# radio_FM.net
KiCad netlist of a schematic drawn in EAGLE
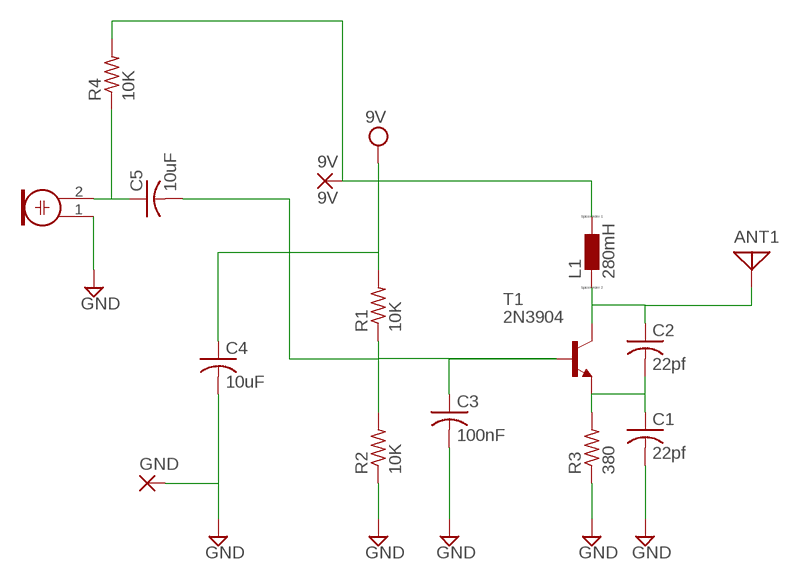
[diagram p0: schematic, sheet 1]

(export (version "E")
  (design (tool "Eeschema 10.0.6"))
  (components
    (comp (ref "9V")
      (value "9V")
      (footprint "eagle-import:1,6_0,8")
      (libsource (lib "eagle-import") (part "1,6/0,8"))
    )
    (comp (ref "ANT1")
      (value "ANTENNA")
      (footprint "eagle-import:PAD-01")
      (libsource (lib "eagle-import") (part "ANTENNA"))
    )
    (comp (ref "C1")
      (value "22pf")
      (footprint "eagle-import:C050-025X075")
      (libsource (lib "eagle-import") (part "C-US050-025X075"))
    )
    (comp (ref "C2")
      (value "22pf")
      (footprint "eagle-import:C050-025X075")
      (libsource (lib "eagle-import") (part "C-US050-025X075"))
    )
    (comp (ref "C3")
      (value "100nF")
      (footprint "eagle-import:C050-025X075")
      (libsource (lib "eagle-import") (part "C-US050-025X075"))
    )
    (comp (ref "C4")
      (value "10uF")
      (footprint "eagle-import:C050-025X075")
      (libsource (lib "eagle-import") (part "C-US050-025X075"))
    )
    (comp (ref "C5")
      (value "10uF")
      (footprint "eagle-import:C050-025X075")
      (libsource (lib "eagle-import") (part "C-US050-025X075"))
    )
    (comp (ref "GND")
      (value "1,6/0,8")
      (footprint "eagle-import:1,6_0,8")
      (libsource (lib "eagle-import") (part "1,6/0,8"))
    )
    (comp (ref "L1")
      (value "280mH")
      (footprint "eagle-import:0207_10")
      (libsource (lib "eagle-import") (part "L0207/10"))
    )
    (comp (ref "M1")
      (value "ELECTRET_MICROPHON-F6035AP")
      (footprint "eagle-import:F6035AP")
      (libsource (lib "eagle-import") (part "ELECTRET_MICROPHON-F6035AP"))
    )
    (comp (ref "R1")
      (value "10K")
      (footprint "eagle-import:0207_7")
      (libsource (lib "eagle-import") (part "R-US_0207/7"))
    )
    (comp (ref "R2")
      (value "10K")
      (footprint "eagle-import:0207_7")
      (libsource (lib "eagle-import") (part "R-US_0207/7"))
    )
    (comp (ref "R3")
      (value "380")
      (footprint "eagle-import:0207_7")
      (libsource (lib "eagle-import") (part "R-US_0207/7"))
    )
    (comp (ref "R4")
      (value "10K")
      (footprint "eagle-import:0207_7")
      (libsource (lib "eagle-import") (part "R-US_0207/7"))
    )
    (comp (ref "T1")
      (value "2N3904")
      (footprint "eagle-import:TO92")
      (libsource (lib "eagle-import") (part "2N3904"))
    )
  )
  (nets
    (net (code "1") (name "9V") (class "Default")
      (node (ref "9V") (pin "1") (pinfunction "P_1") (pintype "passive"))
      (node (ref "C4") (pin "1") (pinfunction "1_1") (pintype "passive"))
      (node (ref "L1") (pin "1") (pinfunction "1_1") (pintype "passive"))
      (node (ref "R1") (pin "2") (pinfunction "2_2") (pintype "passive"))
      (node (ref "R4") (pin "2") (pinfunction "2_2") (pintype "passive"))
    )
    (net (code "2") (name "GND") (class "Default")
      (node (ref "C1") (pin "2") (pinfunction "2_2") (pintype "passive"))
      (node (ref "C3") (pin "2") (pinfunction "2_2") (pintype "passive"))
      (node (ref "C4") (pin "2") (pinfunction "2_2") (pintype "passive"))
      (node (ref "GND") (pin "1") (pinfunction "P_1") (pintype "passive"))
      (node (ref "M1") (pin "1") (pinfunction "1_1") (pintype "passive"))
      (node (ref "R2") (pin "1") (pinfunction "1_1") (pintype "passive"))
      (node (ref "R3") (pin "1") (pinfunction "1_1") (pintype "passive"))
    )
    (net (code "3") (name "Net-(C5-Pad1)") (class "Default")
      (node (ref "C5") (pin "1") (pinfunction "1_1") (pintype "passive"))
      (node (ref "M1") (pin "2") (pinfunction "2_2") (pintype "passive"))
      (node (ref "R4") (pin "1") (pinfunction "1_1") (pintype "passive"))
    )
    (net (code "4") (name "Net-(T1-B)") (class "Default")
      (node (ref "C3") (pin "1") (pinfunction "1_1") (pintype "passive"))
      (node (ref "C5") (pin "2") (pinfunction "2_2") (pintype "passive"))
      (node (ref "R1") (pin "1") (pinfunction "1_1") (pintype "passive"))
      (node (ref "R2") (pin "2") (pinfunction "2_2") (pintype "passive"))
      (node (ref "T1") (pin "2") (pinfunction "B_2") (pintype "passive"))
    )
    (net (code "5") (name "Net-(T1-C)") (class "Default")
      (node (ref "ANT1") (pin "1") (pinfunction "1_1") (pintype "output"))
      (node (ref "C2") (pin "1") (pinfunction "1_1") (pintype "passive"))
      (node (ref "L1") (pin "2") (pinfunction "2_2") (pintype "passive"))
      (node (ref "T1") (pin "1") (pinfunction "C_1") (pintype "passive"))
    )
    (net (code "6") (name "Net-(T1-E)") (class "Default")
      (node (ref "C1") (pin "1") (pinfunction "1_1") (pintype "passive"))
      (node (ref "C2") (pin "2") (pinfunction "2_2") (pintype "passive"))
      (node (ref "R3") (pin "2") (pinfunction "2_2") (pintype "passive"))
      (node (ref "T1") (pin "3") (pinfunction "E_3") (pintype "passive"))
    )
  )
)
